# Power_supply.net
KiCad netlist of a schematic drawn in Altium Designer
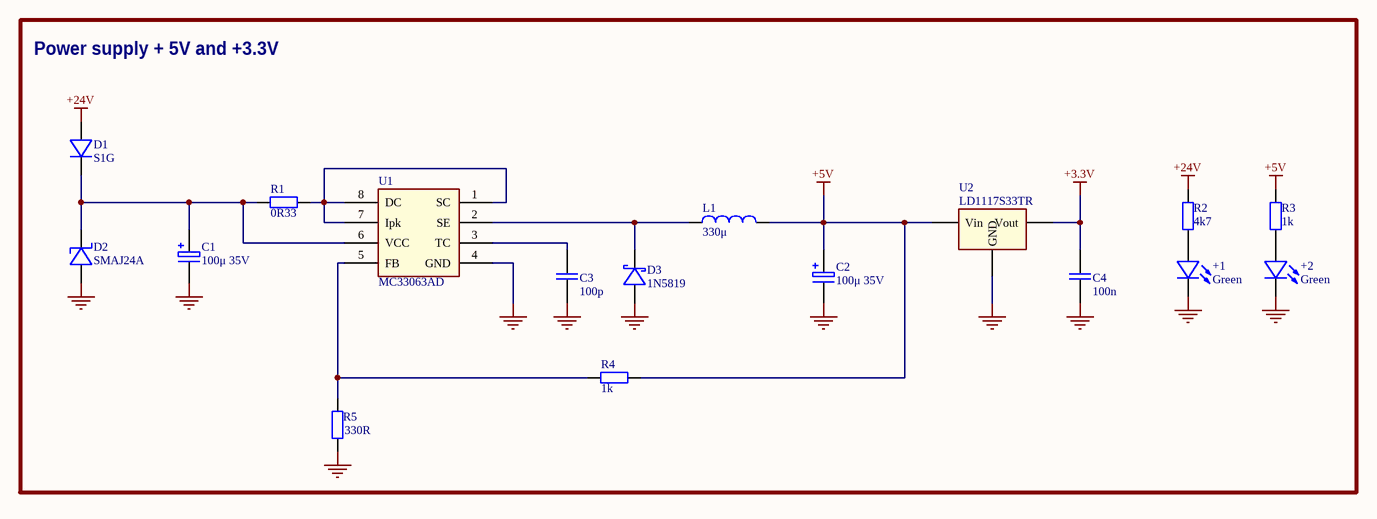
[diagram p0: Power supply.SchDoc]

(export (version "E")
  (design (tool "Eeschema 10.0.6"))
  (components
    (comp (ref "+1")
      (value "Green")
      (footprint "D LED green 0805")
      (description "LED green SMD 0805")
      (libsource (lib "Komponente") (part "D LED green"))
    )
    (comp (ref "+2")
      (value "Green")
      (footprint "D LED green 0805")
      (description "LED green SMD 0805")
      (libsource (lib "Komponente") (part "D LED green"))
    )
    (comp (ref "C1")
      (value "100μ 35V")
      (footprint "Cap Pol Size D")
      (description "Electrolytic Capacitor 100uF 35V SMD size D")
      (libsource (lib "Komponente") (part "Cap Al El 100uF 35V SMD size D"))
    )
    (comp (ref "C2")
      (value "100μ 35V")
      (footprint "Cap Pol Size D")
      (description "Electrolytic Capacitor 100uF 35V SMD size D")
      (libsource (lib "Komponente") (part "Cap Al El 100uF 35V SMD size D"))
    )
    (comp (ref "C3")
      (value "100p")
      (footprint "Cap 0805")
      (description "Capacitor 100pF 50V 0805 SMD")
      (libsource (lib "Komponente") (part "Cap 100pF 50V 0805 SMD"))
    )
    (comp (ref "C4")
      (value "100n")
      (footprint "Cap 0805")
      (description "Capacitor 100nF 50V 0805 SMD")
      (libsource (lib "Komponente") (part "Cap 100nF 50V 0805 SMD"))
    )
    (comp (ref "D1")
      (value "S1G")
      (footprint "DO-214AC (SMA)")
      (description "Diode SMD DO-214AC (SMA)")
      (libsource (lib "Komponente") (part "D S1G"))
    )
    (comp (ref "D2")
      (value "SMAJ24A")
      (footprint "DO-214AC (SMA)")
      (description "Diode SMD DO-214AC (SMA)")
      (libsource (lib "Komponente") (part "D SMAJ24A"))
    )
    (comp (ref "D3")
      (value "1N5819")
      (footprint "SOD-123")
      (description "Diode SMD SOD-123")
      (libsource (lib "Komponente") (part "D 1N5819"))
    )
    (comp (ref "L1")
      (value "330μ")
      (footprint "SRR1050A")
      (description "Inductor 330uH VLP8040T-331M SMD")
      (libsource (lib "Komponente") (part "Inductor 330uH VLP8040T-331M SMD"))
    )
    (comp (ref "R1")
      (value "0R33")
      (footprint "Res 0805")
      (description "Resistor 0R33 0805 SMD")
      (libsource (lib "Komponente") (part "Res 0R33 0805 SMD"))
    )
    (comp (ref "R2")
      (value "4k7")
      (footprint "Res 0805")
      (description "Resistor 4k7 0805 SMD")
      (libsource (lib "Komponente") (part "Res 4k7 0805 SMD"))
    )
    (comp (ref "R3")
      (value "1k")
      (footprint "Res 0805")
      (description "Resistor 1k 0805 SMD")
      (libsource (lib "") (part "Res 1k 0805 SMD_1"))
    )
    (comp (ref "R4")
      (value "1k")
      (footprint "Res 0805")
      (description "Resistor 1k 0805 SMD")
      (libsource (lib "Komponente") (part "Res 1k 0805 SMD"))
    )
    (comp (ref "R5")
      (value "330R")
      (footprint "Res 0805")
      (description "Resistor 330k 1% 0805 SMD")
      (libsource (lib "Komponente") (part "Res 330k 1% 0805 SMD"))
    )
    (comp (ref "U1")
      (value "MC33063AD")
      (footprint "SOIC-8")
      (description "Switching regulator, SOIC 8-pin, -40°C to +85°C")
      (libsource (lib "Integrirane_komponente") (part "MC33063AD"))
    )
    (comp (ref "U2")
      (value "LD1117S33TR")
      (footprint "SOT-223 (Tab=Pin 2)")
      (description "Voltage regulator, 3.3 V, 800 mA, SOT-223")
      (libsource (lib "Integrirane_komponente") (part "LD1117S33TR"))
    )
  )
  (nets
    (net (code "1") (name "+3.3V") (class "Default")
      (node (ref "C4") (pin "1") (pinfunction "1_1") (pintype "passive"))
      (node (ref "U2") (pin "2") (pinfunction "Vout_2") (pintype "passive"))
    )
    (net (code "2") (name "+5V") (class "Default")
      (node (ref "C2") (pin "1") (pinfunction "1_1") (pintype "passive"))
      (node (ref "L1") (pin "2") (pinfunction "2_2") (pintype "passive"))
      (node (ref "R3") (pin "2") (pinfunction "2_2") (pintype "passive"))
      (node (ref "R4") (pin "2") (pinfunction "2_2") (pintype "passive"))
      (node (ref "U2") (pin "3") (pinfunction "Vin_3") (pintype "passive"))
    )
    (net (code "3") (name "+24V") (class "Default")
      (node (ref "D1") (pin "2") (pinfunction "2_2") (pintype "passive"))
      (node (ref "R2") (pin "2") (pinfunction "2_2") (pintype "passive"))
    )
    (net (code "4") (name "GND") (class "Default")
      (node (ref "+1") (pin "1") (pinfunction "1_1") (pintype "passive"))
      (node (ref "+2") (pin "1") (pinfunction "1_1") (pintype "passive"))
      (node (ref "C1") (pin "2") (pinfunction "2_2") (pintype "passive"))
      (node (ref "C2") (pin "2") (pinfunction "2_2") (pintype "passive"))
      (node (ref "C3") (pin "2") (pinfunction "2_2") (pintype "passive"))
      (node (ref "C4") (pin "2") (pinfunction "2_2") (pintype "passive"))
      (node (ref "D2") (pin "2") (pinfunction "2_2") (pintype "passive"))
      (node (ref "D3") (pin "A") (pinfunction "A_A") (pintype "passive"))
      (node (ref "R5") (pin "1") (pinfunction "1_1") (pintype "passive"))
      (node (ref "U1") (pin "4") (pinfunction "GND_4") (pintype "passive"))
      (node (ref "U2") (pin "1") (pinfunction "GND_1") (pintype "passive"))
    )
    (net (code "5") (name "Net-(+1-Pad2)") (class "Default")
      (node (ref "+1") (pin "2") (pinfunction "2_2") (pintype "passive"))
      (node (ref "R2") (pin "1") (pinfunction "1_1") (pintype "passive"))
    )
    (net (code "6") (name "Net-(+2-Pad2)") (class "Default")
      (node (ref "+2") (pin "2") (pinfunction "2_2") (pintype "passive"))
      (node (ref "R3") (pin "1") (pinfunction "1_1") (pintype "passive"))
    )
    (net (code "7") (name "Net-(U1-DC)") (class "Default")
      (node (ref "R1") (pin "2") (pinfunction "2_2") (pintype "passive"))
      (node (ref "U1") (pin "1") (pinfunction "SC_1") (pintype "passive"))
      (node (ref "U1") (pin "7") (pinfunction "Ipk_7") (pintype "passive"))
      (node (ref "U1") (pin "8") (pinfunction "DC_8") (pintype "passive"))
    )
    (net (code "8") (name "Net-(U1-FB)") (class "Default")
      (node (ref "R4") (pin "1") (pinfunction "1_1") (pintype "passive"))
      (node (ref "R5") (pin "2") (pinfunction "2_2") (pintype "passive"))
      (node (ref "U1") (pin "5") (pinfunction "FB_5") (pintype "passive"))
    )
    (net (code "9") (name "Net-(U1-SE)") (class "Default")
      (node (ref "D3") (pin "K") (pinfunction "K_K") (pintype "passive"))
      (node (ref "L1") (pin "1") (pinfunction "1_1") (pintype "passive"))
      (node (ref "U1") (pin "2") (pinfunction "SE_2") (pintype "passive"))
    )
    (net (code "10") (name "Net-(U1-TC)") (class "Default")
      (node (ref "C3") (pin "1") (pinfunction "1_1") (pintype "passive"))
      (node (ref "U1") (pin "3") (pinfunction "TC_3") (pintype "passive"))
    )
    (net (code "11") (name "Net-(U1-VCC)") (class "Default")
      (node (ref "C1") (pin "1") (pinfunction "1_1") (pintype "passive"))
      (node (ref "D1") (pin "1") (pinfunction "1_1") (pintype "passive"))
      (node (ref "D2") (pin "1") (pinfunction "1_1") (pintype "passive"))
      (node (ref "R1") (pin "1") (pinfunction "1_1") (pintype "passive"))
      (node (ref "U1") (pin "6") (pinfunction "VCC_6") (pintype "passive"))
    )
  )
)
